# 5V_POWER.net
KiCad netlist of a schematic drawn in Altium Designer
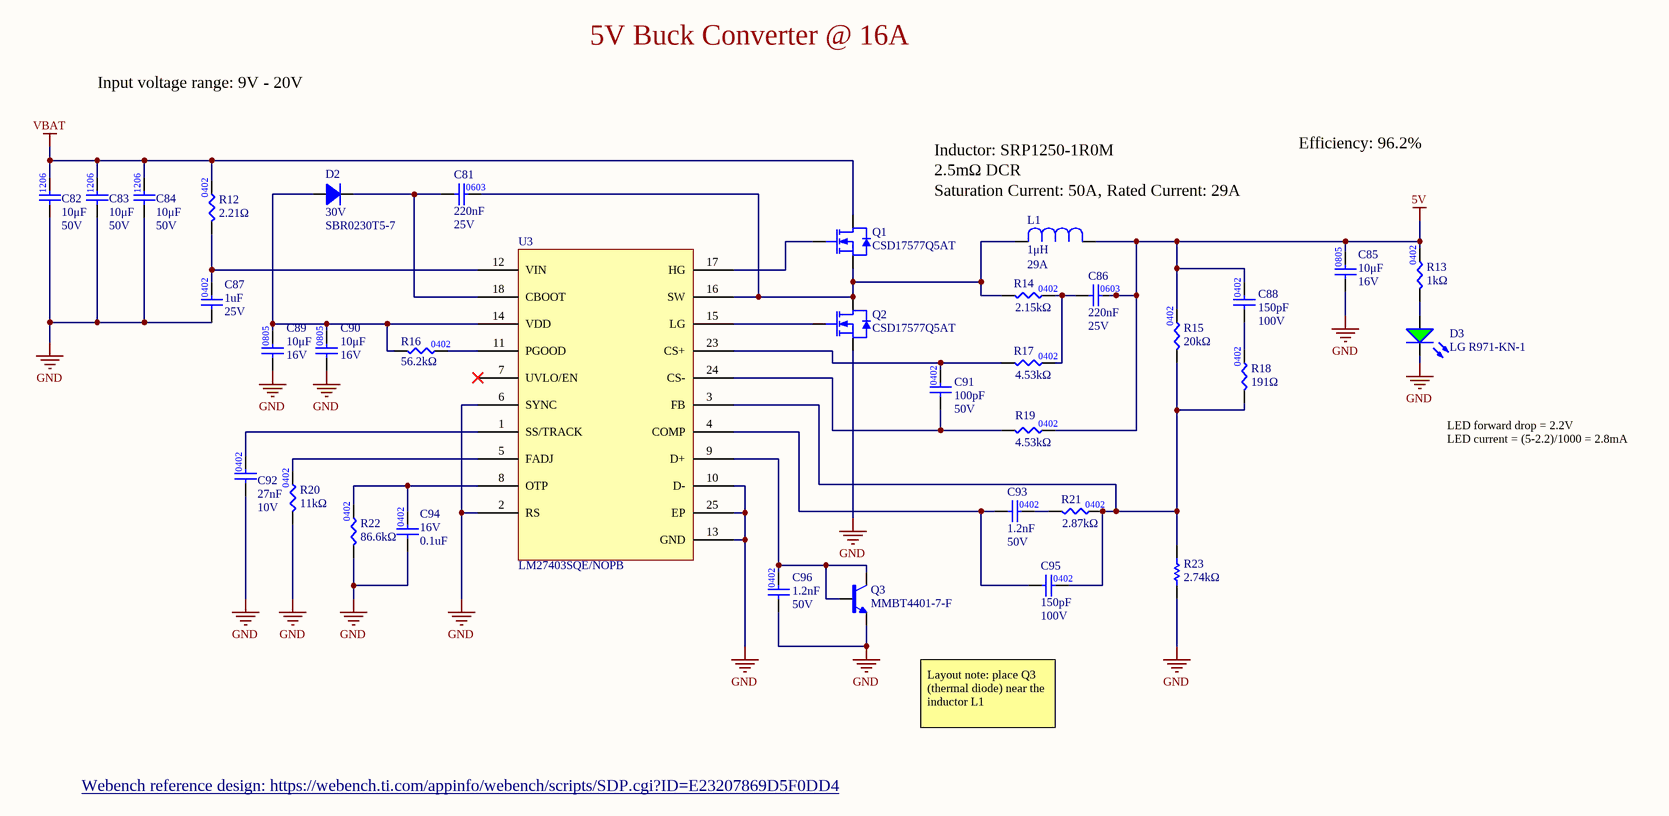
[diagram p0: 5V POWER.SchDoc]

(export (version "E")
  (design (tool "Eeschema 10.0.6"))
  (components
    (comp (ref "C81")
      (value "CAP_0.22uF_25V_X5R_0402")
      (footprint "CAP0402")
      (description "0.22 µF ±10% 25V Ceramic Capacitor X5R 0402 (1005 Metric)")
      (fields
        (field (name "MANUFACTURER") "Yageo")
        (field (name "MANUFACTURER PART NUMBER") "CC0402KRX5R8BB224")
        (field (name "CAPACITANCE") "220nF")
        (field (name "RATED DC VOLTAGE (URDC)") "25V")
      )
      (libsource (lib "UWRT_Schematic_Library_2020") (part "CAP_0.22uF_25V_X5R_0402"))
    )
    (comp (ref "C82")
      (value "10μF")
      (footprint "CAP1210")
      (description "CAP CER 10UF 50V X7R 1210")
      (fields (field (name "VOLTAGE RATING") "50V") (field (name "Comment") "CAP_10uF_50V_1210"))
      (libsource (lib "UWRT_Schematic_Library_2020") (part "CAP_10uF_50V_1210"))
    )
    (comp (ref "C83")
      (value "10μF")
      (footprint "CAP1210")
      (description "CAP CER 10UF 50V X7R 1210")
      (fields (field (name "VOLTAGE RATING") "50V") (field (name "Comment") "CAP_10uF_50V_1210"))
      (libsource (lib "UWRT_Schematic_Library_2020") (part "CAP_10uF_50V_1210"))
    )
    (comp (ref "C84")
      (value "10μF")
      (footprint "CAP1210")
      (description "CAP CER 10UF 50V X7R 1210")
      (fields (field (name "VOLTAGE RATING") "50V") (field (name "Comment") "CAP_10uF_50V_1210"))
      (libsource (lib "UWRT_Schematic_Library_2020") (part "CAP_10uF_50V_1210"))
    )
    (comp (ref "C85")
      (value "10μF")
      (footprint "CAP2012")
      (description "CAP CER 10UF 16V X5R 0805")
      (fields (field (name "VOLTAGE RATING") "16V") (field (name "Comment") "CAP_10uF_16V_0805"))
      (libsource (lib "UWRT_Schematic_Library_2020") (part "CAP_10uF_16V_0805"))
    )
    (comp (ref "C86")
      (value "CAP_0.22uF_25V_X5R_0402")
      (footprint "CAP0402")
      (description "0.22 µF ±10% 25V Ceramic Capacitor X5R 0402 (1005 Metric)")
      (fields
        (field (name "MANUFACTURER") "Yageo")
        (field (name "MANUFACTURER PART NUMBER") "CC0402KRX5R8BB224")
        (field (name "CAPACITANCE") "220nF")
        (field (name "RATED DC VOLTAGE (URDC)") "25V")
      )
      (libsource (lib "UWRT_Schematic_Library_2020") (part "CAP_0.22uF_25V_X5R_0402"))
    )
    (comp (ref "C87")
      (value "CAP_1uF_25V_0402")
      (footprint "CAP0402")
      (description "±10% 25V Ceramic Capacitor X5R 0402 (1005 Metric)")
      (fields (field (name "CAPACITANCE") "1uF") (field (name "VOLTAGE") "25V"))
      (libsource (lib "UWRT_Schematic_Library_2020") (part "CAP_1uF_25V_0402"))
    )
    (comp (ref "C88")
      (value "CAP_150pF_100V_NP0_0402")
      (footprint "CAP0402")
      (description "±5% 100V Ceramic Capacitor C0G, NP0 0402 (1005 Metric)")
      (fields
        (field (name "MANUFACTURER") "Yageo")
        (field (name "MANUFACTURER PART NUMBER") "CGA2B2C0G2A151J050BE")
        (field (name "CAPACITANCE") "150pF")
        (field (name "RATED DC VOLTAGE (URDC)") "100V")
      )
      (libsource (lib "UWRT_Schematic_Library_2020") (part "CAP_150pF_100V_NP0_0402"))
    )
    (comp (ref "C89")
      (value "10μF")
      (footprint "CAP2012")
      (description "CAP CER 10UF 16V X5R 0805")
      (fields (field (name "VOLTAGE RATING") "16V") (field (name "Comment") "CAP_10uF_16V_0805"))
      (libsource (lib "UWRT_Schematic_Library_2020") (part "CAP_10uF_16V_0805"))
    )
    (comp (ref "C90")
      (value "10μF")
      (footprint "CAP2012")
      (description "CAP CER 10UF 16V X5R 0805")
      (fields (field (name "VOLTAGE RATING") "16V") (field (name "Comment") "CAP_10uF_16V_0805"))
      (libsource (lib "UWRT_Schematic_Library_2020") (part "CAP_10uF_16V_0805"))
    )
    (comp (ref "C91")
      (value "CAP_100pF_50V_0402")
      (footprint "CAP0402")
      (description "100 pF ±10% 50V Ceramic Capacitor X7R 0402 (1005 Metric)")
      (fields (field (name "CAPACITANCE") "100pF") (field (name "VOLTAGE") "50V"))
      (libsource (lib "UWRT_Schematic_Library_2020") (part "CAP_100pF_50V_0402"))
    )
    (comp (ref "C92")
      (value "CAP_0.027uF_10V_X7R_0402")
      (footprint "CAP0402")
      (description "0.027 µF ±10% 10V Ceramic Capacitor X7R 0402 (1005 Metric)")
      (fields
        (field (name "MANUFACTURER") "Yageo")
        (field (name "MANUFACTURER PART NUMBER") "CC0402KRX7R6BB273")
        (field (name "CAPACITANCE") "27nF")
        (field (name "RATED DC VOLTAGE (URDC)") "10V")
      )
      (libsource (lib "UWRT_Schematic_Library_2020") (part "CAP_0.027uF_10V_X7R_0402"))
    )
    (comp (ref "C93")
      (value "CAP_1.2nF_50V_X7R_0402")
      (footprint "CAP0402")
      (description "1200 pF ±5% 50V Ceramic Capacitor X7R 0402 (1005 Metric)")
      (fields
        (field (name "MANUFACTURER") "Yageo")
        (field (name "MANUFACTURER PART NUMBER") "CC0402JRX7R9BB122")
        (field (name "CAPACITANCE") "1.2nF")
        (field (name "RATED DC VOLTAGE (URDC)") "50V")
      )
      (libsource (lib "UWRT_Schematic_Library_2020") (part "CAP_1.2nF_50V_X7R_0402"))
    )
    (comp (ref "C94")
      (value "CAP_0.1uF_16V_X7R_0402")
      (footprint "CAP0402")
      (description "Ceramic Capacitor, Ceramic")
      (fields
        (field (name "MANUFACTURER") "Taiyo Yuden")
        (field (name "MANUFACTURER PART NUMBER") "LMK212AC6106MD-T")
        (field (name "RATED DC VOLTAGE (URDC)") "16V")
        (field (name "CAPACITANCE") "0.1uF")
      )
      (libsource (lib "UWRT_Schematic_Library_2020") (part "CAP_0.1uF_16V_X7R_0402"))
    )
    (comp (ref "C95")
      (value "CAP_150pF_100V_NP0_0402")
      (footprint "CAP0402")
      (description "±5% 100V Ceramic Capacitor C0G, NP0 0402 (1005 Metric)")
      (fields
        (field (name "MANUFACTURER") "Yageo")
        (field (name "MANUFACTURER PART NUMBER") "CGA2B2C0G2A151J050BE")
        (field (name "CAPACITANCE") "150pF")
        (field (name "RATED DC VOLTAGE (URDC)") "100V")
      )
      (libsource (lib "UWRT_Schematic_Library_2020") (part "CAP_150pF_100V_NP0_0402"))
    )
    (comp (ref "C96")
      (value "CAP_1.2nF_50V_X7R_0402")
      (footprint "CAP0402")
      (description "1200 pF ±5% 50V Ceramic Capacitor X7R 0402 (1005 Metric)")
      (fields
        (field (name "MANUFACTURER") "Yageo")
        (field (name "MANUFACTURER PART NUMBER") "CC0402JRX7R9BB122")
        (field (name "CAPACITANCE") "1.2nF")
        (field (name "RATED DC VOLTAGE (URDC)") "50V")
      )
      (libsource (lib "UWRT_Schematic_Library_2020") (part "CAP_1.2nF_50V_X7R_0402"))
    )
    (comp (ref "D2")
      (value "30V")
      (footprint "SOD523")
      (description "Diode Super Barrier 30 V 200mA Surface Mount SOD-523")
      (fields
        (field (name "MANUFACTURER PART NUMBER 1") "SBR0230T5-7")
        (field (name "Comment") "SBR0230T5-7")
      )
      (libsource (lib "UWRT_Schematic_Library_2020") (part "DIO_30V_200mA"))
    )
    (comp (ref "D3")
      (value "DIO_LED_G")
      (footprint "LED_0805_GREEN")
      (description "LED GREEN DIFFUSED 0805 SMD")
      (fields (field (name "MANUFACTURER PART NUMBER 1") "LG R971-KN-1"))
      (libsource (lib "UWRT_Schematic_Library_2020") (part "DIO_LED_G"))
    )
    (comp (ref "L1")
      (value "IND_1uH_29A")
      (footprint "IND_BOURNS_SRP1250")
      (description "FIXED IND 1UH 29A 2.5 MOHM SMD")
      (fields (field (name "CURRENT RATING") "29A") (field (name "INDUCTANCE") "1μH"))
      (libsource (lib "UWRT_Schematic_Library_2020") (part "IND_1uH_29A"))
    )
    (comp (ref "Q1")
      (value "NMOS_30V_60A")
      (footprint "MOSFET_CSD19531Q5A")
      (description "MOSFET N-CH 30V 60A 8VSON")
      (fields (field (name "MANUFACTURER PART NUMBER 1") "CSD17577Q5AT"))
      (libsource (lib "UWRT_Schematic_Library_2020") (part "NMOS_30V_60A"))
    )
    (comp (ref "Q2")
      (value "NMOS_30V_60A")
      (footprint "MOSFET_CSD19531Q5A")
      (description "MOSFET N-CH 30V 60A 8VSON")
      (fields (field (name "MANUFACTURER PART NUMBER 1") "CSD17577Q5AT"))
      (libsource (lib "UWRT_Schematic_Library_2020") (part "NMOS_30V_60A"))
    )
    (comp (ref "Q3")
      (value "MMBT4401-7-F")
      (footprint "MMBT4401-7-F")
      (description "Bipolar (BJT) Transistor NPN 40 V 600 mA 250MHz 310 mW Surface Mount SOT-23-3")
      (libsource (lib "UWRT_Schematic_Library_2020") (part "MMBT4401-7-F"))
    )
    (comp (ref "R12")
      (value "2.21Ω")
      (footprint "RES0402")
      (description "RES 2.21 OHM 1% 1/16W 0402")
      (fields (field (name "POWER") "0.063W, 1/16W") (field (name "TOLERANCE") "1%"))
      (libsource (lib "UWRT_Schematic_Library_2020") (part "RES_2.21Ω_0402_1%"))
    )
    (comp (ref "R13")
      (value "RES_1kΩ_0402")
      (footprint "RES0402")
      (fields
        (field (name "MANUFACTURER") "Stackpole Electronics")
        (field (name "MANUFACTURER PART NUMBER") "RMCF0402FT1K00")
        (field (name "TOLERANCE") "1%")
        (field (name "RESISTANCE") "1kΩ")
      )
      (libsource (lib "UWRT_Schematic_Library_2020") (part "RES_1kΩ_0402"))
    )
    (comp (ref "R14")
      (value "2.15kΩ")
      (footprint "RES0402")
      (description "RES SMD 2.15K OHM 1% 1/16W 0402")
      (fields (field (name "POWER") "0.063W, 1/16W") (field (name "TOLERANCE") "1%"))
      (libsource (lib "UWRT_Schematic_Library_2020") (part "RES_2.15kΩ_0402_1%"))
    )
    (comp (ref "R15")
      (value "20kΩ")
      (footprint "RES0402")
      (description "RES SMD 20K OHM 1% 1/16W 0402")
      (fields (field (name "POWER") "0.063W, 1/16W") (field (name "TOLERANCE") "1%"))
      (libsource (lib "UWRT_Schematic_Library_2020") (part "RES_20kΩ_0402_1%"))
    )
    (comp (ref "R16")
      (value "56.2kΩ")
      (footprint "RES0402")
      (description "RES SMD 56.2K OHM 1% 1/16W 0402")
      (fields (field (name "POWER") "0.063W, 1/16W") (field (name "TOLERANCE") "1%"))
      (libsource (lib "UWRT_Schematic_Library_2020") (part "RES_56.2kΩ_0402_1%"))
    )
    (comp (ref "R17")
      (value "4.53kΩ")
      (footprint "RES0402")
      (description "RES SMD 4.53K OHM 1% 1/16W 0402")
      (fields (field (name "TOLERANCE") "1%") (field (name "Comment") "RES_4.53kΩ_0402_1%"))
      (libsource (lib "UWRT_Schematic_Library_2020") (part "RES_4.53kΩ_0402_1%"))
    )
    (comp (ref "R18")
      (value "191Ω")
      (footprint "RES0402")
      (description "RES SMD 191 OHM 1% 1/16W 0402")
      (fields (field (name "POWER") "0.063W, 1/16W") (field (name "TOLERANCE") "1%"))
      (libsource (lib "UWRT_Schematic_Library_2020") (part "RES_191Ω_0402_1%"))
    )
    (comp (ref "R19")
      (value "4.53kΩ")
      (footprint "RES0402")
      (description "RES SMD 4.53K OHM 1% 1/16W 0402")
      (fields (field (name "TOLERANCE") "1%") (field (name "Comment") "RES_4.53kΩ_0402_1%"))
      (libsource (lib "UWRT_Schematic_Library_2020") (part "RES_4.53kΩ_0402_1%"))
    )
    (comp (ref "R20")
      (value "11kΩ")
      (footprint "RES0402")
      (description "RES 11K OHM 1% 1/16W 0402")
      (fields (field (name "POWER") "0.063W, 1/16W") (field (name "TOLERANCE") "1%"))
      (libsource (lib "UWRT_Schematic_Library_2020") (part "RES_11kΩ_0402_1%"))
    )
    (comp (ref "R21")
      (value "2.87kΩ")
      (footprint "RES0402")
      (description "RES SMD 2.87K OHM 1% 1/16W 0402")
      (fields (field (name "TOLERANCE") "1%") (field (name "Comment") "RES_2.87kΩ_0402_1%"))
      (libsource (lib "UWRT_Schematic_Library_2020") (part "RES_2.87kΩ_0402_1%"))
    )
    (comp (ref "R22")
      (value "86.6kΩ")
      (footprint "RES0402")
      (description "RES SMD 86.6K OHM 1% 1/16W 0402")
      (fields (field (name "POWER") "0.063W, 1/16W") (field (name "TOLERANCE") "1%"))
      (libsource (lib "UWRT_Schematic_Library_2020") (part "RES_86.6kΩ_0402_1%"))
    )
    (comp (ref "R23")
      (value "2.74kΩ")
      (footprint "RES0402")
      (description "RES 2.74K OHM 1% 1/16W 0402")
      (fields (field (name "POWER") "0.063W, 1/16W") (field (name "TOLERANCE") "1%"))
      (libsource (lib "UWRT_Schematic_Library_2020") (part "RES_2.74kΩ_0402_1%"))
    )
    (comp (ref "U3")
      (value "LM27403SQE/NOPB")
      (footprint "QFN50P400X400X80-25N")
      (description "Buck Regulator Positive Output Step-Down - DC-DC Controller IC 24-WQFN (4x4)")
      (libsource (lib "UWRT_Schematic_Library_2020") (part "LM27403SQE/NOPB"))
    )
  )
  (nets
    (net (code "1") (name "5V") (class "Default")
      (node (ref "C85") (pin "2") (pinfunction "2_2") (pintype "passive"))
      (node (ref "C86") (pin "2") (pinfunction "2_2") (pintype "passive"))
      (node (ref "C88") (pin "2") (pinfunction "2_2") (pintype "passive"))
      (node (ref "L1") (pin "1") (pinfunction "1_1") (pintype "passive"))
      (node (ref "R13") (pin "2") (pinfunction "2_2") (pintype "passive"))
      (node (ref "R15") (pin "2") (pinfunction "2_2") (pintype "passive"))
      (node (ref "R19") (pin "2") (pinfunction "2_2") (pintype "passive"))
    )
    (net (code "2") (name "GND") (class "Default")
      (node (ref "C82") (pin "1") (pinfunction "1_1") (pintype "passive"))
      (node (ref "C83") (pin "1") (pinfunction "1_1") (pintype "passive"))
      (node (ref "C84") (pin "1") (pinfunction "1_1") (pintype "passive"))
      (node (ref "C85") (pin "1") (pinfunction "1_1") (pintype "passive"))
      (node (ref "C87") (pin "1") (pinfunction "1_1") (pintype "passive"))
      (node (ref "C89") (pin "1") (pinfunction "1_1") (pintype "passive"))
      (node (ref "C90") (pin "1") (pinfunction "1_1") (pintype "passive"))
      (node (ref "C92") (pin "1") (pinfunction "1_1") (pintype "passive"))
      (node (ref "C94") (pin "1") (pinfunction "1_1") (pintype "passive"))
      (node (ref "C96") (pin "1") (pinfunction "1_1") (pintype "passive"))
      (node (ref "D3") (pin "2") (pinfunction "K_2") (pintype "passive"))
      (node (ref "Q2") (pin "1") (pinfunction "Source_1") (pintype "passive"))
      (node (ref "Q3") (pin "2") (pinfunction "2_2") (pintype "passive"))
      (node (ref "R20") (pin "1") (pinfunction "1_1") (pintype "passive"))
      (node (ref "R22") (pin "1") (pinfunction "1_1") (pintype "passive"))
      (node (ref "R23") (pin "1") (pinfunction "1_1") (pintype "passive"))
      (node (ref "U3") (pin "10") (pinfunction "D-_10") (pintype "passive"))
      (node (ref "U3") (pin "13") (pinfunction "GND_13") (pintype "passive"))
      (node (ref "U3") (pin "2") (pinfunction "RS_2") (pintype "passive"))
      (node (ref "U3") (pin "25") (pinfunction "EP_25") (pintype "passive"))
      (node (ref "U3") (pin "6") (pinfunction "SYNC_6") (pintype "passive"))
    )
    (net (code "3") (name "Net-(C86-Pad1)") (class "Default")
      (node (ref "C86") (pin "1") (pinfunction "1_1") (pintype "passive"))
      (node (ref "R14") (pin "2") (pinfunction "2_2") (pintype "passive"))
      (node (ref "R17") (pin "2") (pinfunction "2_2") (pintype "passive"))
    )
    (net (code "4") (name "Net-(C88-Pad1)") (class "Default")
      (node (ref "C88") (pin "1") (pinfunction "1_1") (pintype "passive"))
      (node (ref "R18") (pin "2") (pinfunction "2_2") (pintype "passive"))
    )
    (net (code "5") (name "Net-(C93-Pad2)") (class "Default")
      (node (ref "C93") (pin "2") (pinfunction "2_2") (pintype "passive"))
      (node (ref "R21") (pin "1") (pinfunction "1_1") (pintype "passive"))
    )
    (net (code "6") (name "Net-(D3-A)") (class "Default")
      (node (ref "D3") (pin "1") (pinfunction "A_1") (pintype "passive"))
      (node (ref "R13") (pin "1") (pinfunction "1_1") (pintype "passive"))
    )
    (net (code "7") (name "Net-(Q1-Gate)") (class "Default")
      (node (ref "Q1") (pin "2") (pinfunction "Gate_2") (pintype "passive"))
      (node (ref "U3") (pin "17") (pinfunction "HG_17") (pintype "passive"))
    )
    (net (code "8") (name "Net-(Q1-Source)") (class "Default")
      (node (ref "C81") (pin "2") (pinfunction "2_2") (pintype "passive"))
      (node (ref "L1") (pin "2") (pinfunction "2_2") (pintype "passive"))
      (node (ref "Q1") (pin "1") (pinfunction "Source_1") (pintype "passive"))
      (node (ref "Q2") (pin "3") (pinfunction "Drain_3") (pintype "passive"))
      (node (ref "R14") (pin "1") (pinfunction "1_1") (pintype "passive"))
      (node (ref "U3") (pin "16") (pinfunction "SW_16") (pintype "passive"))
    )
    (net (code "9") (name "Net-(Q2-Gate)") (class "Default")
      (node (ref "Q2") (pin "2") (pinfunction "Gate_2") (pintype "passive"))
      (node (ref "U3") (pin "15") (pinfunction "LG_15") (pintype "passive"))
    )
    (net (code "10") (name "Net-(U3-CBOOT)") (class "Default")
      (node (ref "C81") (pin "1") (pinfunction "1_1") (pintype "passive"))
      (node (ref "D2") (pin "1") (pintype "passive"))
      (node (ref "U3") (pin "18") (pinfunction "CBOOT_18") (pintype "passive"))
    )
    (net (code "11") (name "Net-(U3-COMP)") (class "Default")
      (node (ref "C93") (pin "1") (pinfunction "1_1") (pintype "passive"))
      (node (ref "C95") (pin "1") (pinfunction "1_1") (pintype "passive"))
      (node (ref "U3") (pin "4") (pinfunction "COMP_4") (pintype "passive"))
    )
    (net (code "12") (name "Net-(U3-CS+)") (class "Default")
      (node (ref "C91") (pin "2") (pinfunction "2_2") (pintype "passive"))
      (node (ref "R17") (pin "1") (pinfunction "1_1") (pintype "passive"))
      (node (ref "U3") (pin "23") (pinfunction "CS+_23") (pintype "passive"))
    )
    (net (code "13") (name "Net-(U3-CS-)") (class "Default")
      (node (ref "C91") (pin "1") (pinfunction "1_1") (pintype "passive"))
      (node (ref "R19") (pin "1") (pinfunction "1_1") (pintype "passive"))
      (node (ref "U3") (pin "24") (pinfunction "CS-_24") (pintype "passive"))
    )
    (net (code "14") (name "Net-(U3-D+)") (class "Default")
      (node (ref "C96") (pin "2") (pinfunction "2_2") (pintype "passive"))
      (node (ref "Q3") (pin "1") (pinfunction "1_1") (pintype "passive"))
      (node (ref "Q3") (pin "3") (pinfunction "3_3") (pintype "passive"))
      (node (ref "U3") (pin "9") (pinfunction "D+_9") (pintype "passive"))
    )
    (net (code "15") (name "Net-(U3-FADJ)") (class "Default")
      (node (ref "R20") (pin "2") (pinfunction "2_2") (pintype "passive"))
      (node (ref "U3") (pin "5") (pinfunction "FADJ_5") (pintype "passive"))
    )
    (net (code "16") (name "Net-(U3-FB)") (class "Default")
      (node (ref "C95") (pin "2") (pinfunction "2_2") (pintype "passive"))
      (node (ref "R15") (pin "1") (pinfunction "1_1") (pintype "passive"))
      (node (ref "R18") (pin "1") (pinfunction "1_1") (pintype "passive"))
      (node (ref "R21") (pin "2") (pinfunction "2_2") (pintype "passive"))
      (node (ref "R23") (pin "2") (pinfunction "2_2") (pintype "passive"))
      (node (ref "U3") (pin "3") (pinfunction "FB_3") (pintype "passive"))
    )
    (net (code "17") (name "Net-(U3-OTP)") (class "Default")
      (node (ref "C94") (pin "2") (pinfunction "2_2") (pintype "passive"))
      (node (ref "R22") (pin "2") (pinfunction "2_2") (pintype "passive"))
      (node (ref "U3") (pin "8") (pinfunction "OTP_8") (pintype "passive"))
    )
    (net (code "18") (name "Net-(U3-PGOOD)") (class "Default")
      (node (ref "R16") (pin "2") (pinfunction "2_2") (pintype "passive"))
      (node (ref "U3") (pin "11") (pinfunction "PGOOD_11") (pintype "passive"))
    )
    (net (code "19") (name "Net-(U3-SS{slash}TRACK)") (class "Default")
      (node (ref "C92") (pin "2") (pinfunction "2_2") (pintype "passive"))
      (node (ref "U3") (pin "1") (pinfunction "SS/TRACK_1") (pintype "passive"))
    )
    (net (code "20") (name "Net-(U3-VDD)") (class "Default")
      (node (ref "C89") (pin "2") (pinfunction "2_2") (pintype "passive"))
      (node (ref "C90") (pin "2") (pinfunction "2_2") (pintype "passive"))
      (node (ref "D2") (pin "2") (pintype "passive"))
      (node (ref "R16") (pin "1") (pinfunction "1_1") (pintype "passive"))
      (node (ref "U3") (pin "14") (pinfunction "VDD_14") (pintype "passive"))
    )
    (net (code "21") (name "Net-(U3-VIN)") (class "Default")
      (node (ref "C87") (pin "2") (pinfunction "2_2") (pintype "passive"))
      (node (ref "R12") (pin "1") (pinfunction "1_1") (pintype "passive"))
      (node (ref "U3") (pin "12") (pinfunction "VIN_12") (pintype "passive"))
    )
    (net (code "22") (name "VBAT") (class "Default")
      (node (ref "C82") (pin "2") (pinfunction "2_2") (pintype "passive"))
      (node (ref "C83") (pin "2") (pinfunction "2_2") (pintype "passive"))
      (node (ref "C84") (pin "2") (pinfunction "2_2") (pintype "passive"))
      (node (ref "Q1") (pin "3") (pinfunction "Drain_3") (pintype "passive"))
      (node (ref "R12") (pin "2") (pinfunction "2_2") (pintype "passive"))
    )
    (net (code "23") (name "unconnected-(U3-UVLO{slash}EN-Pad7)") (class "Default")
      (node (ref "U3") (pin "7") (pinfunction "UVLO/EN_7") (pintype "passive+no_connect"))
    )
  )
)
